# MCU-Board.net
KiCad netlist of a schematic drawn in Altium Designer
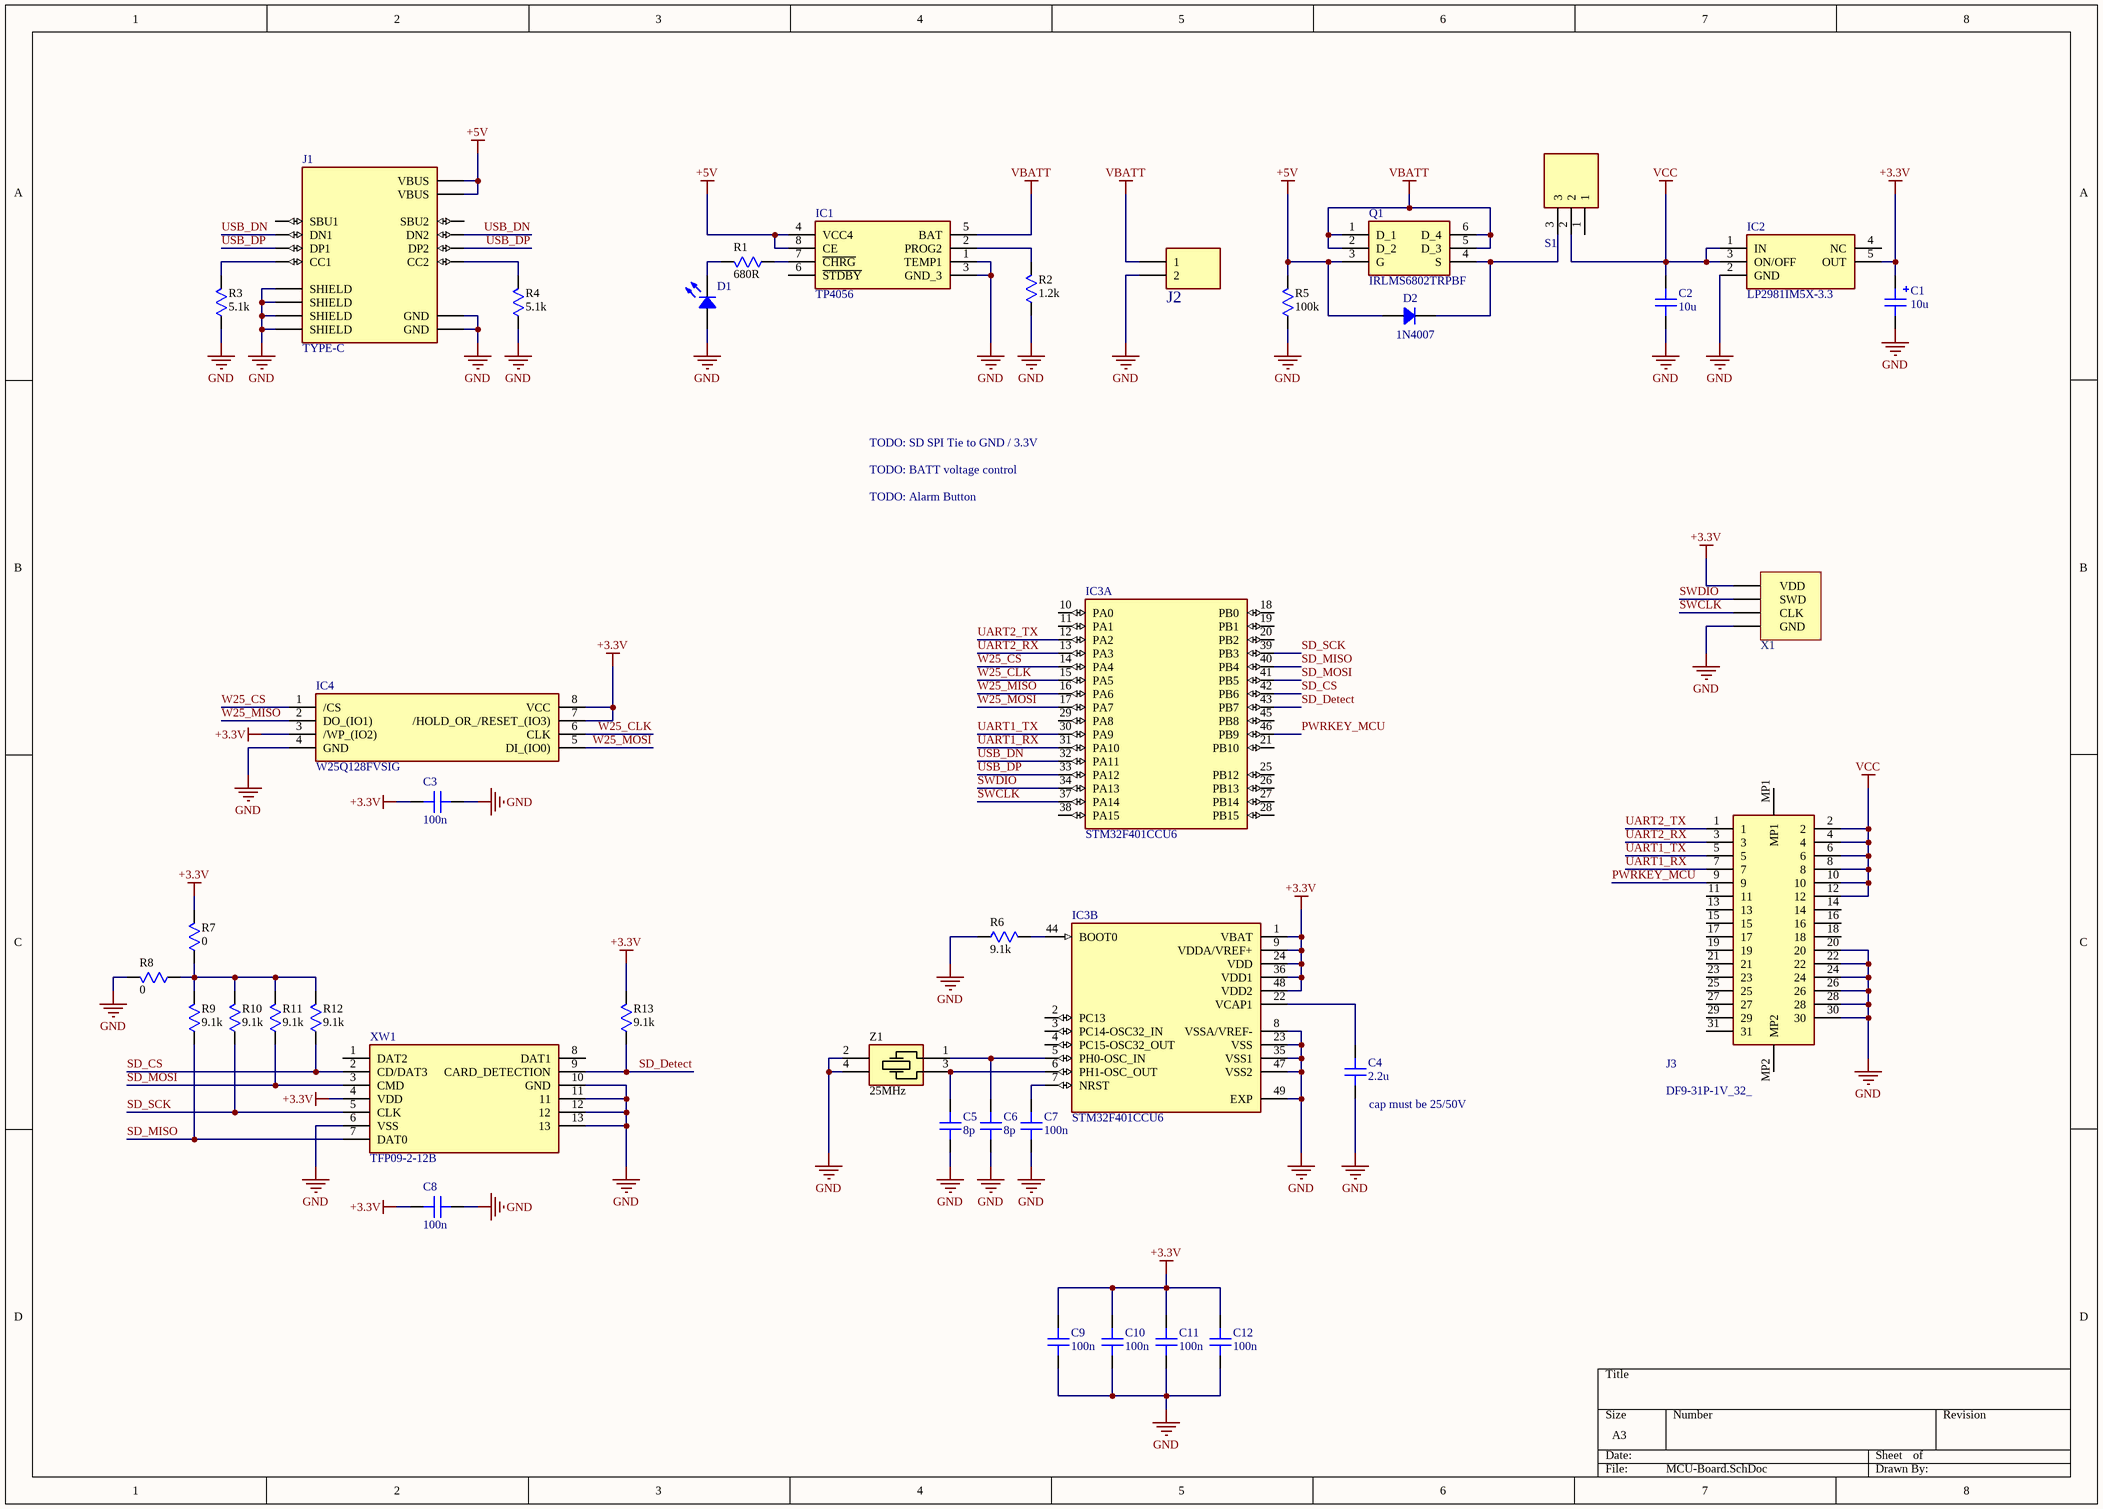
[diagram p0: MCU-Board.SchDoc]

(export (version "E")
  (design (tool "Eeschema 10.0.6"))
  (components
    (comp (ref "C1")
      (value "10u")
      (footprint "PcbLib:CAP: TANTAL-A")
      (description "SMD Capacitor Polar")
      (libsource (lib "Schlib") (part "Capacitor_polar"))
    )
    (comp (ref "C2")
      (value "10u")
      (footprint "PcbLib:CAP: 0805")
      (description "SMD Capacitor")
      (libsource (lib "Schlib") (part "Capacitor"))
    )
    (comp (ref "C3")
      (value "100n")
      (footprint "PcbLib:CAP: 0603")
      (description "SMD Capacitor")
      (libsource (lib "Schlib") (part "Capacitor"))
    )
    (comp (ref "C4")
      (value "2.2u")
      (footprint "PcbLib:CAP: 0805")
      (description "SMD Capacitor")
      (libsource (lib "Schlib") (part "Capacitor"))
    )
    (comp (ref "C5")
      (value "8p")
      (footprint "PcbLib:CAP: 0603")
      (description "SMD Capacitor")
      (libsource (lib "Schlib") (part "Capacitor"))
    )
    (comp (ref "C6")
      (value "8p")
      (footprint "PcbLib:CAP: 0603")
      (description "SMD Capacitor")
      (libsource (lib "Schlib") (part "Capacitor"))
    )
    (comp (ref "C7")
      (value "100n")
      (footprint "PcbLib:CAP: 0603")
      (description "SMD Capacitor")
      (libsource (lib "Schlib") (part "Capacitor"))
    )
    (comp (ref "C8")
      (value "100n")
      (footprint "PcbLib:CAP: 0603")
      (description "SMD Capacitor")
      (libsource (lib "Schlib") (part "Capacitor"))
    )
    (comp (ref "C9")
      (value "100n")
      (footprint "PcbLib:CAP: 0603")
      (description "SMD Capacitor")
      (libsource (lib "Schlib") (part "Capacitor"))
    )
    (comp (ref "C10")
      (value "100n")
      (footprint "PcbLib:CAP: 0603")
      (description "SMD Capacitor")
      (libsource (lib "Schlib") (part "Capacitor"))
    )
    (comp (ref "C11")
      (value "100n")
      (footprint "PcbLib:CAP: 0603")
      (description "SMD Capacitor")
      (libsource (lib "Schlib") (part "Capacitor"))
    )
    (comp (ref "C12")
      (value "100n")
      (footprint "PcbLib:CAP: 0603")
      (description "SMD Capacitor")
      (libsource (lib "Schlib") (part "Capacitor"))
    )
    (comp (ref "D1")
      (value "~")
      (footprint "PcbLib:LED 0603_1608")
      (description "Chip LED")
      (libsource (lib "Schlib") (part "LED"))
    )
    (comp (ref "D2")
      (value "1N4007")
      (footprint "PcbLib:DIODE: SMA")
      (description "Rectifier Diode")
      (libsource (lib "Schlib") (part "Diode"))
    )
    (comp (ref "IC1")
      (value "TP4056")
      (footprint "PcbLib:SOIC127P600X175-9N")
      (description "Connector")
      (libsource (lib "Schlib") (part "TP4056"))
    )
    (comp (ref "IC2")
      (value "LP2981IM5X-3.3")
      (footprint "PcbLib:SOT95P280X145-5N")
      (description "Integrated Circuit")
      (fields
        (field (name "MANUFACTURER_PART_NUMBER") "LP2981IM5X-5.0")
        (field (name "MOUSER PART NUMBER") "926-LP2981IM5X-50")
      )
      (libsource (lib "Schlib") (part "LP2981IM5X-3.3"))
    )
    (comp (ref "IC3")
      (value "STM32F401CCU6")
      (footprint "PcbLib:QFN50P700X700X60-49N-D")
      (description "Integrated Circuit")
      (fields (field (name "MOUSER PART NUMBER") "511-STM32F401CCU6"))
      (libsource (lib "Schlib") (part "STM32F401CCU6"))
    )
    (comp (ref "IC4")
      (value "W25Q128FVSIG")
      (footprint "PcbLib:SOIC127P790X216-8N")
      (description "Integrated Circuit")
      (libsource (lib "Schlib") (part "W25Q128FVSIG"))
    )
    (comp (ref "J1")
      (value "TYPE-C")
      (footprint "PcbLib:HRO_TYPE-C-31-M-12")
      (description "USB Connectors 24 Receptacle 1 8.94*7.3mm RoHS")
      (fields (field (name "MP") "TYPE-C-31-M-12"))
      (libsource (lib "Schlib") (part "TYPE-C-31-M-12"))
    )
    (comp (ref "J2")
      (value "NX1500-02SMR")
      (footprint "PcbLib:NX1500-02SMR")
      (libsource (lib "Schlib") (part "NX1500-02SMR"))
    )
    (comp (ref "J3")
      (value "DF9-31P-1V_32_")
      (footprint "PcbLib:DF931P1V32")
      (description "Connector")
      (fields
        (field (name "MANUFACTURER_PART_NUMBER") "DF9-31P-1V(32)")
        (field (name "MOUSER PART NUMBER") "798-DF9-31P-1V32")
      )
      (libsource (lib "Schlib") (part "DF9-31P-1V_32_"))
    )
    (comp (ref "Q1")
      (value "IRLMS6802TRPBF")
      (footprint "PcbLib:SOT95P280X130-6N")
      (description "MOSFET (P-Channel)")
      (fields (field (name "MOUSER PART NUMBER") "942-IRLMS6802TRPBF"))
      (libsource (lib "Schlib") (part "IRLMS6802TRPBF"))
    )
    (comp (ref "R1")
      (value "680R")
      (footprint "PcbLib:RES: 0603")
      (fields
        (field (name "MANUFACTURER") "Yageo")
        (field (name "PARTNUMBER") "RC0201JR-07100RL")
        (field (name "VALUEMANUFACTURERPARTNUMBER") "Resistor film, 680R, , 0201, 0.05W, -55...+125°C")
      )
      (libsource (lib "Schlib") (part "Resistor"))
    )
    (comp (ref "R2")
      (value "1.2k")
      (footprint "PcbLib:RES: 0805")
      (fields
        (field (name "MANUFACTURER") "Yageo")
        (field (name "PARTNUMBER") "RC0201JR-07100RL")
        (field (name "VALUEMANUFACTURERPARTNUMBER") "Resistor film, 1.2k, , 0201, 0.05W, -55...+125°C")
      )
      (libsource (lib "Schlib") (part "Resistor"))
    )
    (comp (ref "R3")
      (value "5.1k")
      (footprint "PcbLib:RES: 0603")
      (fields
        (field (name "MANUFACTURER") "Yageo")
        (field (name "PARTNUMBER") "RC0201JR-07100RL")
        (field (name "VALUEMANUFACTURERPARTNUMBER") "Resistor film, 5.1k, , 0201, 0.05W, -55...+125°C")
      )
      (libsource (lib "Schlib") (part "Resistor"))
    )
    (comp (ref "R4")
      (value "5.1k")
      (footprint "PcbLib:RES: 0603")
      (fields
        (field (name "MANUFACTURER") "Yageo")
        (field (name "PARTNUMBER") "RC0201JR-07100RL")
        (field (name "VALUEMANUFACTURERPARTNUMBER") "Resistor film, 5.1k, , 0201, 0.05W, -55...+125°C")
      )
      (libsource (lib "Schlib") (part "Resistor"))
    )
    (comp (ref "R5")
      (value "100k")
      (footprint "PcbLib:RES: 0603")
      (fields
        (field (name "MANUFACTURER") "Yageo")
        (field (name "PARTNUMBER") "RC0201JR-07100RL")
        (field (name "VALUEMANUFACTURERPARTNUMBER") "Resistor film, 100k, , 0201, 0.05W, -55...+125°C")
      )
      (libsource (lib "Schlib") (part "Resistor"))
    )
    (comp (ref "R6")
      (value "9.1k")
      (footprint "PcbLib:RES: 0603")
      (fields
        (field (name "MANUFACTURER") "Yageo")
        (field (name "PARTNUMBER") "RC0201JR-07100RL")
        (field (name "VALUEMANUFACTURERPARTNUMBER") "Resistor film, 9.1k, , 0201, 0.05W, -55...+125°C")
      )
      (libsource (lib "Schlib") (part "Resistor"))
    )
    (comp (ref "R7")
      (value "0")
      (footprint "PcbLib:RES: 0603")
      (fields
        (field (name "MANUFACTURER") "Yageo")
        (field (name "PARTNUMBER") "RC0201JR-07100RL")
        (field (name "VALUEMANUFACTURERPARTNUMBER") "Resistor film, 0, , 0201, 0.05W, -55...+125°C")
      )
      (libsource (lib "Schlib") (part "Resistor"))
    )
    (comp (ref "R8")
      (value "0")
      (footprint "PcbLib:RES: 0603")
      (fields
        (field (name "MANUFACTURER") "Yageo")
        (field (name "PARTNUMBER") "RC0201JR-07100RL")
        (field (name "VALUEMANUFACTURERPARTNUMBER") "Resistor film, 0, , 0201, 0.05W, -55...+125°C")
      )
      (libsource (lib "Schlib") (part "Resistor"))
    )
    (comp (ref "R9")
      (value "9.1k")
      (footprint "PcbLib:RES: 0603")
      (fields
        (field (name "MANUFACTURER") "Yageo")
        (field (name "PARTNUMBER") "RC0201JR-07100RL")
        (field (name "VALUEMANUFACTURERPARTNUMBER") "Resistor film, 9.1k, , 0201, 0.05W, -55...+125°C")
      )
      (libsource (lib "Schlib") (part "Resistor"))
    )
    (comp (ref "R10")
      (value "9.1k")
      (footprint "PcbLib:RES: 0603")
      (fields
        (field (name "MANUFACTURER") "Yageo")
        (field (name "PARTNUMBER") "RC0201JR-07100RL")
        (field (name "VALUEMANUFACTURERPARTNUMBER") "Resistor film, 9.1k, , 0201, 0.05W, -55...+125°C")
      )
      (libsource (lib "Schlib") (part "Resistor"))
    )
    (comp (ref "R11")
      (value "9.1k")
      (footprint "PcbLib:RES: 0603")
      (fields
        (field (name "MANUFACTURER") "Yageo")
        (field (name "PARTNUMBER") "RC0201JR-07100RL")
        (field (name "VALUEMANUFACTURERPARTNUMBER") "Resistor film, 9.1k, , 0201, 0.05W, -55...+125°C")
      )
      (libsource (lib "Schlib") (part "Resistor"))
    )
    (comp (ref "R12")
      (value "9.1k")
      (footprint "PcbLib:RES: 0603")
      (fields
        (field (name "MANUFACTURER") "Yageo")
        (field (name "PARTNUMBER") "RC0201JR-07100RL")
        (field (name "VALUEMANUFACTURERPARTNUMBER") "Resistor film, 9.1k, , 0201, 0.05W, -55...+125°C")
      )
      (libsource (lib "Schlib") (part "Resistor"))
    )
    (comp (ref "R13")
      (value "9.1k")
      (footprint "PcbLib:RES: 0603")
      (fields
        (field (name "MANUFACTURER") "Yageo")
        (field (name "PARTNUMBER") "RC0201JR-07100RL")
        (field (name "VALUEMANUFACTURERPARTNUMBER") "Resistor film, 9.1k, , 0201, 0.05W, -55...+125°C")
      )
      (libsource (lib "Schlib") (part "Resistor"))
    )
    (comp (ref "S1")
      (value "OS102011MA1QN1")
      (footprint "PcbLib:OS102011MA1QN1")
      (description "Switch")
      (fields (field (name "MOUSER PART NUMBER") "611-OS102011MA1QN1"))
      (libsource (lib "Schlib") (part "OS102011MA1QN1"))
    )
    (comp (ref "X1")
      (value "~")
      (footprint "PcbLib:CON: PLS-4R")
      (description "SWD Interface")
      (libsource (lib "Schlib") (part "Connector SWD"))
    )
    (comp (ref "XW1")
      (value "TFP09-2-12B")
      (footprint "PcbLib:TFP09212B")
      (description "Connector")
      (libsource (lib "Schlib") (part "TFP09-2-12B"))
    )
    (comp (ref "Z1")
      (value "~")
      (footprint "PcbLib:OSC: 3225")
      (fields
        (field (name "MANUFACTURER") "Murata Electronics")
        (field (name "PARTNUMBER") "XRCGB25M000F0L00R0")
        (field (name "VALUEMANUFACTURERPARTNUMBER") "Crystal, 25MHz, 6pF, ±50ppm, case 2016, -30...+85°C")
        (field (name "FREQUENCY") "25MHz")
      )
      (libsource (lib "Schlib") (part "Crystal"))
    )
  )
  (nets
    (net (code "1") (name "+3.3V") (class "Default")
      (node (ref "C1") (pin "1") (pinfunction "1_1") (pintype "passive"))
      (node (ref "C10") (pin "2") (pinfunction "2_2") (pintype "passive"))
      (node (ref "C11") (pin "2") (pinfunction "2_2") (pintype "passive"))
      (node (ref "C12") (pin "2") (pinfunction "2_2") (pintype "passive"))
      (node (ref "C3") (pin "2") (pinfunction "2_2") (pintype "passive"))
      (node (ref "C8") (pin "2") (pinfunction "2_2") (pintype "passive"))
      (node (ref "C9") (pin "2") (pinfunction "2_2") (pintype "passive"))
      (node (ref "IC2") (pin "5") (pinfunction "OUT_5") (pintype "passive"))
      (node (ref "IC3") (pin "1") (pinfunction "VBAT_1") (pintype "power_in"))
      (node (ref "IC3") (pin "24") (pinfunction "VDD_24") (pintype "power_in"))
      (node (ref "IC3") (pin "36") (pinfunction "VDD1_36") (pintype "power_in"))
      (node (ref "IC3") (pin "48") (pinfunction "VDD2_48") (pintype "power_in"))
      (node (ref "IC3") (pin "9") (pinfunction "VDDA/VREF+_9") (pintype "power_in"))
      (node (ref "IC4") (pin "3") (pinfunction "/WP_(IO2)_3") (pintype "passive"))
      (node (ref "IC4") (pin "7") (pinfunction "/HOLD_OR_/RESET_(IO3)_7") (pintype "passive"))
      (node (ref "IC4") (pin "8") (pinfunction "VCC_8") (pintype "passive"))
      (node (ref "R13") (pin "2") (pinfunction "2_2") (pintype "passive"))
      (node (ref "R7") (pin "2") (pinfunction "2_2") (pintype "passive"))
      (node (ref "X1") (pin "1") (pinfunction "VDD_1") (pintype "power_in"))
      (node (ref "XW1") (pin "4") (pinfunction "VDD_4") (pintype "passive"))
    )
    (net (code "2") (name "+5V") (class "Default")
      (node (ref "D2") (pin "1") (pinfunction "1_1") (pintype "passive"))
      (node (ref "IC1") (pin "4") (pinfunction "VCC4_4") (pintype "passive"))
      (node (ref "IC1") (pin "8") (pinfunction "CE_8") (pintype "passive"))
      (node (ref "J1") (pin "A4B9") (pinfunction "VBUS_A4B9") (pintype "power_in"))
      (node (ref "J1") (pin "B4A9") (pinfunction "VBUS_B4A9") (pintype "power_in"))
      (node (ref "Q1") (pin "3") (pinfunction "G_3") (pintype "passive"))
      (node (ref "R5") (pin "2") (pinfunction "2_2") (pintype "passive"))
    )
    (net (code "3") (name "/PWRKEY_MCU") (class "Default")
      (node (ref "IC3") (pin "46") (pinfunction "PB9_46") (pintype "bidirectional"))
      (node (ref "J3") (pin "9") (pinfunction "9_9") (pintype "passive"))
    )
    (net (code "4") (name "/SD_CS") (class "Default")
      (node (ref "IC3") (pin "42") (pinfunction "PB6_42") (pintype "bidirectional"))
      (node (ref "R12") (pin "1") (pinfunction "1_1") (pintype "passive"))
      (node (ref "XW1") (pin "2") (pinfunction "CD/DAT3_2") (pintype "passive"))
    )
    (net (code "5") (name "/SD_Detect") (class "Default")
      (node (ref "IC3") (pin "43") (pinfunction "PB7_43") (pintype "bidirectional"))
      (node (ref "R13") (pin "1") (pinfunction "1_1") (pintype "passive"))
      (node (ref "XW1") (pin "9") (pinfunction "CARD_DETECTION_9") (pintype "passive"))
    )
    (net (code "6") (name "/SD_MISO") (class "Default")
      (node (ref "IC3") (pin "40") (pinfunction "PB4_40") (pintype "bidirectional"))
      (node (ref "R9") (pin "1") (pinfunction "1_1") (pintype "passive"))
      (node (ref "XW1") (pin "7") (pinfunction "DAT0_7") (pintype "passive"))
    )
    (net (code "7") (name "/SD_MOSI") (class "Default")
      (node (ref "IC3") (pin "41") (pinfunction "PB5_41") (pintype "bidirectional"))
      (node (ref "R11") (pin "1") (pinfunction "1_1") (pintype "passive"))
      (node (ref "XW1") (pin "3") (pinfunction "CMD_3") (pintype "passive"))
    )
    (net (code "8") (name "/SD_SCK") (class "Default")
      (node (ref "IC3") (pin "39") (pinfunction "PB3_39") (pintype "bidirectional"))
      (node (ref "R10") (pin "1") (pinfunction "1_1") (pintype "passive"))
      (node (ref "XW1") (pin "5") (pinfunction "CLK_5") (pintype "passive"))
    )
    (net (code "9") (name "/SWCLK") (class "Default")
      (node (ref "IC3") (pin "37") (pinfunction "PA14_37") (pintype "bidirectional"))
      (node (ref "X1") (pin "3") (pinfunction "CLK_3") (pintype "passive"))
    )
    (net (code "10") (name "/SWDIO") (class "Default")
      (node (ref "IC3") (pin "34") (pinfunction "PA13_34") (pintype "bidirectional"))
      (node (ref "X1") (pin "2") (pinfunction "SWD_2") (pintype "passive"))
    )
    (net (code "11") (name "/UART1_RX") (class "Default")
      (node (ref "IC3") (pin "31") (pinfunction "PA10_31") (pintype "bidirectional"))
      (node (ref "J3") (pin "7") (pinfunction "7_7") (pintype "passive"))
    )
    (net (code "12") (name "/UART1_TX") (class "Default")
      (node (ref "IC3") (pin "30") (pinfunction "PA9_30") (pintype "bidirectional"))
      (node (ref "J3") (pin "5") (pinfunction "5_5") (pintype "passive"))
    )
    (net (code "13") (name "/UART2_RX") (class "Default")
      (node (ref "IC3") (pin "13") (pinfunction "PA3_13") (pintype "bidirectional"))
      (node (ref "J3") (pin "3") (pinfunction "3_3") (pintype "passive"))
    )
    (net (code "14") (name "/UART2_TX") (class "Default")
      (node (ref "IC3") (pin "12") (pinfunction "PA2_12") (pintype "bidirectional"))
      (node (ref "J3") (pin "1") (pinfunction "1_1") (pintype "passive"))
    )
    (net (code "15") (name "/USB_DN") (class "Default")
      (node (ref "IC3") (pin "32") (pinfunction "PA11_32") (pintype "bidirectional"))
      (node (ref "J1") (pin "A7") (pinfunction "DN1_A7") (pintype "bidirectional"))
      (node (ref "J1") (pin "B7") (pinfunction "DN2_B7") (pintype "bidirectional"))
    )
    (net (code "16") (name "/USB_DP") (class "Default")
      (node (ref "IC3") (pin "33") (pinfunction "PA12_33") (pintype "bidirectional"))
      (node (ref "J1") (pin "A6") (pinfunction "DP1_A6") (pintype "bidirectional"))
      (node (ref "J1") (pin "B6") (pinfunction "DP2_B6") (pintype "bidirectional"))
    )
    (net (code "17") (name "/W25_CLK") (class "Default")
      (node (ref "IC3") (pin "15") (pinfunction "PA5_15") (pintype "bidirectional"))
      (node (ref "IC4") (pin "6") (pinfunction "CLK_6") (pintype "passive"))
    )
    (net (code "18") (name "/W25_CS") (class "Default")
      (node (ref "IC3") (pin "14") (pinfunction "PA4_14") (pintype "bidirectional"))
      (node (ref "IC4") (pin "1") (pinfunction "/CS_1") (pintype "passive"))
    )
    (net (code "19") (name "/W25_MISO") (class "Default")
      (node (ref "IC3") (pin "16") (pinfunction "PA6_16") (pintype "bidirectional"))
      (node (ref "IC4") (pin "2") (pinfunction "DO_(IO1)_2") (pintype "passive"))
    )
    (net (code "20") (name "/W25_MOSI") (class "Default")
      (node (ref "IC3") (pin "17") (pinfunction "PA7_17") (pintype "bidirectional"))
      (node (ref "IC4") (pin "5") (pinfunction "DI_(IO0)_5") (pintype "passive"))
    )
    (net (code "21") (name "GND") (class "Default")
      (node (ref "C1") (pin "2") (pinfunction "2_2") (pintype "passive"))
      (node (ref "C10") (pin "1") (pinfunction "1_1") (pintype "passive"))
      (node (ref "C11") (pin "1") (pinfunction "1_1") (pintype "passive"))
      (node (ref "C12") (pin "1") (pinfunction "1_1") (pintype "passive"))
      (node (ref "C2") (pin "1") (pinfunction "1_1") (pintype "passive"))
      (node (ref "C3") (pin "1") (pinfunction "1_1") (pintype "passive"))
      (node (ref "C4") (pin "1") (pinfunction "1_1") (pintype "passive"))
      (node (ref "C5") (pin "1") (pinfunction "1_1") (pintype "passive"))
      (node (ref "C6") (pin "2") (pinfunction "2_2") (pintype "passive"))
      (node (ref "C7") (pin "1") (pinfunction "1_1") (pintype "passive"))
      (node (ref "C8") (pin "1") (pinfunction "1_1") (pintype "passive"))
      (node (ref "C9") (pin "1") (pinfunction "1_1") (pintype "passive"))
      (node (ref "D1") (pin "1") (pinfunction "1_1") (pintype "passive"))
      (node (ref "IC1") (pin "1") (pinfunction "TEMP1_1") (pintype "passive"))
      (node (ref "IC1") (pin "3") (pinfunction "GND_3_3") (pintype "passive"))
      (node (ref "IC2") (pin "2") (pinfunction "GND_2") (pintype "passive"))
      (node (ref "IC3") (pin "23") (pinfunction "VSS_23") (pintype "power_in"))
      (node (ref "IC3") (pin "35") (pinfunction "VSS1_35") (pintype "power_in"))
      (node (ref "IC3") (pin "47") (pinfunction "VSS2_47") (pintype "power_in"))
      (node (ref "IC3") (pin "49") (pinfunction "EXP_49") (pintype "power_in"))
      (node (ref "IC3") (pin "8") (pinfunction "VSSA/VREF-_8") (pintype "power_in"))
      (node (ref "IC4") (pin "4") (pinfunction "GND_4") (pintype "passive"))
      (node (ref "J1") (pin "A1B12") (pinfunction "GND_A1B12") (pintype "power_in"))
      (node (ref "J1") (pin "B1A12") (pinfunction "GND_B1A12") (pintype "power_in"))
      (node (ref "J1") (pin "S1") (pinfunction "SHIELD_S1") (pintype "passive"))
      (node (ref "J1") (pin "S2") (pinfunction "SHIELD_S2") (pintype "passive"))
      (node (ref "J1") (pin "S3") (pinfunction "SHIELD_S3") (pintype "passive"))
      (node (ref "J1") (pin "S4") (pinfunction "SHIELD_S4") (pintype "passive"))
      (node (ref "J2") (pin "2") (pinfunction "2_2") (pintype "passive"))
      (node (ref "J3") (pin "20") (pinfunction "20_20") (pintype "passive"))
      (node (ref "J3") (pin "22") (pinfunction "22_22") (pintype "passive"))
      (node (ref "J3") (pin "24") (pinfunction "24_24") (pintype "passive"))
      (node (ref "J3") (pin "26") (pinfunction "26_26") (pintype "passive"))
      (node (ref "J3") (pin "28") (pinfunction "28_28") (pintype "passive"))
      (node (ref "J3") (pin "30") (pinfunction "30_30") (pintype "passive"))
      (node (ref "R2") (pin "1") (pinfunction "1_1") (pintype "passive"))
      (node (ref "R3") (pin "1") (pinfunction "1_1") (pintype "passive"))
      (node (ref "R4") (pin "1") (pinfunction "1_1") (pintype "passive"))
      (node (ref "R5") (pin "1") (pinfunction "1_1") (pintype "passive"))
      (node (ref "R6") (pin "1") (pinfunction "1_1") (pintype "passive"))
      (node (ref "R8") (pin "2") (pinfunction "2_2") (pintype "passive"))
      (node (ref "X1") (pin "4") (pinfunction "GND_4") (pintype "power_in"))
      (node (ref "XW1") (pin "10") (pinfunction "GND_10") (pintype "passive"))
      (node (ref "XW1") (pin "11") (pinfunction "11_11") (pintype "passive"))
      (node (ref "XW1") (pin "12") (pinfunction "12_12") (pintype "passive"))
      (node (ref "XW1") (pin "13") (pinfunction "13_13") (pintype "passive"))
      (node (ref "XW1") (pin "6") (pinfunction "VSS_6") (pintype "passive"))
      (node (ref "Z1") (pin "2") (pinfunction "2_2") (pintype "passive"))
      (node (ref "Z1") (pin "4") (pinfunction "4_4") (pintype "passive"))
    )
    (net (code "22") (name "Net-(D1-Pad2)") (class "Default")
      (node (ref "D1") (pin "2") (pinfunction "2_2") (pintype "passive"))
      (node (ref "R1") (pin "2") (pinfunction "2_2") (pintype "passive"))
    )
    (net (code "23") (name "Net-(IC1-PROG2)") (class "Default")
      (node (ref "IC1") (pin "2") (pinfunction "PROG2_2") (pintype "passive"))
      (node (ref "R2") (pin "2") (pinfunction "2_2") (pintype "passive"))
    )
    (net (code "24") (name "Net-(IC1-~{CHRG})") (class "Default")
      (node (ref "IC1") (pin "7") (pinfunction "~{CHRG}_7") (pintype "passive"))
      (node (ref "R1") (pin "1") (pinfunction "1_1") (pintype "passive"))
    )
    (net (code "25") (name "Net-(IC3B-BOOT0)") (class "Default")
      (node (ref "IC3") (pin "44") (pinfunction "BOOT0_44") (pintype "input"))
      (node (ref "R6") (pin "2") (pinfunction "2_2") (pintype "passive"))
    )
    (net (code "26") (name "Net-(IC3B-NRST)") (class "Default")
      (node (ref "C7") (pin "2") (pinfunction "2_2") (pintype "passive"))
      (node (ref "IC3") (pin "7") (pinfunction "NRST_7") (pintype "bidirectional"))
    )
    (net (code "27") (name "Net-(IC3B-PH0-OSC_IN)") (class "Default")
      (node (ref "C6") (pin "1") (pinfunction "1_1") (pintype "passive"))
      (node (ref "IC3") (pin "5") (pinfunction "PH0-OSC_IN_5") (pintype "bidirectional"))
      (node (ref "Z1") (pin "1") (pinfunction "1_1") (pintype "passive"))
    )
    (net (code "28") (name "Net-(IC3B-PH1-OSC_OUT)") (class "Default")
      (node (ref "C5") (pin "2") (pinfunction "2_2") (pintype "passive"))
      (node (ref "IC3") (pin "6") (pinfunction "PH1-OSC_OUT_6") (pintype "bidirectional"))
      (node (ref "Z1") (pin "3") (pinfunction "3_3") (pintype "passive"))
    )
    (net (code "29") (name "Net-(IC3B-VCAP1)") (class "Default")
      (node (ref "C4") (pin "2") (pinfunction "2_2") (pintype "passive"))
      (node (ref "IC3") (pin "22") (pinfunction "VCAP1_22") (pintype "power_in"))
    )
    (net (code "30") (name "Net-(J1-CC1)") (class "Default")
      (node (ref "J1") (pin "A5") (pinfunction "CC1_A5") (pintype "bidirectional"))
      (node (ref "R3") (pin "2") (pinfunction "2_2") (pintype "passive"))
    )
    (net (code "31") (name "Net-(J1-CC2)") (class "Default")
      (node (ref "J1") (pin "B5") (pinfunction "CC2_B5") (pintype "bidirectional"))
      (node (ref "R4") (pin "2") (pinfunction "2_2") (pintype "passive"))
    )
    (net (code "32") (name "Net-(Q1-S)") (class "Default")
      (node (ref "D2") (pin "2") (pinfunction "2_2") (pintype "passive"))
      (node (ref "Q1") (pin "4") (pinfunction "S_4") (pintype "passive"))
      (node (ref "S1") (pin "3") (pinfunction "3_3") (pintype "passive"))
    )
    (net (code "33") (name "Net-(R10-Pad2)") (class "Default")
      (node (ref "R10") (pin "2") (pinfunction "2_2") (pintype "passive"))
      (node (ref "R11") (pin "2") (pinfunction "2_2") (pintype "passive"))
      (node (ref "R12") (pin "2") (pinfunction "2_2") (pintype "passive"))
      (node (ref "R7") (pin "1") (pinfunction "1_1") (pintype "passive"))
      (node (ref "R8") (pin "1") (pinfunction "1_1") (pintype "passive"))
      (node (ref "R9") (pin "2") (pinfunction "2_2") (pintype "passive"))
    )
    (net (code "34") (name "VBATT") (class "Default")
      (node (ref "IC1") (pin "5") (pinfunction "BAT_5") (pintype "passive"))
      (node (ref "J2") (pin "1") (pinfunction "1_1") (pintype "passive"))
      (node (ref "Q1") (pin "1") (pinfunction "D_1_1") (pintype "passive"))
      (node (ref "Q1") (pin "2") (pinfunction "D_2_2") (pintype "passive"))
      (node (ref "Q1") (pin "5") (pinfunction "D_3_5") (pintype "passive"))
      (node (ref "Q1") (pin "6") (pinfunction "D_4_6") (pintype "passive"))
    )
    (net (code "35") (name "VCC") (class "Default")
      (node (ref "C2") (pin "2") (pinfunction "2_2") (pintype "passive"))
      (node (ref "IC2") (pin "1") (pinfunction "IN_1") (pintype "passive"))
      (node (ref "IC2") (pin "3") (pinfunction "ON/OFF_3") (pintype "passive"))
      (node (ref "J3") (pin "10") (pinfunction "10_10") (pintype "passive"))
      (node (ref "J3") (pin "12") (pinfunction "12_12") (pintype "passive"))
      (node (ref "J3") (pin "2") (pinfunction "2_2") (pintype "passive"))
      (node (ref "J3") (pin "4") (pinfunction "4_4") (pintype "passive"))
      (node (ref "J3") (pin "6") (pinfunction "6_6") (pintype "passive"))
      (node (ref "J3") (pin "8") (pinfunction "8_8") (pintype "passive"))
      (node (ref "S1") (pin "2") (pinfunction "2_2") (pintype "passive"))
    )
    (net (code "36") (name "unconnected-(IC1-~{STDBY}-Pad6)") (class "Default")
      (node (ref "IC1") (pin "6") (pinfunction "~{STDBY}_6") (pintype "passive"))
    )
    (net (code "37") (name "unconnected-(IC2-NC-Pad4)") (class "Default")
      (node (ref "IC2") (pin "4") (pinfunction "NC_4") (pintype "passive"))
    )
    (net (code "38") (name "unconnected-(IC3A-PA0-Pad10)") (class "Default")
      (node (ref "IC3") (pin "10") (pinfunction "PA0_10") (pintype "bidirectional"))
    )
    (net (code "39") (name "unconnected-(IC3A-PA1-Pad11)") (class "Default")
      (node (ref "IC3") (pin "11") (pinfunction "PA1_11") (pintype "bidirectional"))
    )
    (net (code "40") (name "unconnected-(IC3A-PA8-Pad29)") (class "Default")
      (node (ref "IC3") (pin "29") (pinfunction "PA8_29") (pintype "bidirectional"))
    )
    (net (code "41") (name "unconnected-(IC3A-PA15-Pad38)") (class "Default")
      (node (ref "IC3") (pin "38") (pinfunction "PA15_38") (pintype "bidirectional"))
    )
    (net (code "42") (name "unconnected-(IC3A-PB0-Pad18)") (class "Default")
      (node (ref "IC3") (pin "18") (pinfunction "PB0_18") (pintype "bidirectional"))
    )
    (net (code "43") (name "unconnected-(IC3A-PB1-Pad19)") (class "Default")
      (node (ref "IC3") (pin "19") (pinfunction "PB1_19") (pintype "bidirectional"))
    )
    (net (code "44") (name "unconnected-(IC3A-PB2-Pad20)") (class "Default")
      (node (ref "IC3") (pin "20") (pinfunction "PB2_20") (pintype "bidirectional"))
    )
    (net (code "45") (name "unconnected-(IC3A-PB8-Pad45)") (class "Default")
      (node (ref "IC3") (pin "45") (pinfunction "PB8_45") (pintype "bidirectional"))
    )
    (net (code "46") (name "unconnected-(IC3A-PB10-Pad21)") (class "Default")
      (node (ref "IC3") (pin "21") (pinfunction "PB10_21") (pintype "bidirectional"))
    )
    (net (code "47") (name "unconnected-(IC3A-PB12-Pad25)") (class "Default")
      (node (ref "IC3") (pin "25") (pinfunction "PB12_25") (pintype "bidirectional"))
    )
    (net (code "48") (name "unconnected-(IC3A-PB13-Pad26)") (class "Default")
      (node (ref "IC3") (pin "26") (pinfunction "PB13_26") (pintype "bidirectional"))
    )
    (net (code "49") (name "unconnected-(IC3A-PB14-Pad27)") (class "Default")
      (node (ref "IC3") (pin "27") (pinfunction "PB14_27") (pintype "bidirectional"))
    )
    (net (code "50") (name "unconnected-(IC3A-PB15-Pad28)") (class "Default")
      (node (ref "IC3") (pin "28") (pinfunction "PB15_28") (pintype "bidirectional"))
    )
    (net (code "51") (name "unconnected-(IC3B-PC13-Pad2)") (class "Default")
      (node (ref "IC3") (pin "2") (pinfunction "PC13_2") (pintype "bidirectional"))
    )
    (net (code "52") (name "unconnected-(IC3B-PC14-OSC32_IN-Pad3)") (class "Default")
      (node (ref "IC3") (pin "3") (pinfunction "PC14-OSC32_IN_3") (pintype "bidirectional"))
    )
    (net (code "53") (name "unconnected-(IC3B-PC15-OSC32_OUT-Pad4)") (class "Default")
      (node (ref "IC3") (pin "4") (pinfunction "PC15-OSC32_OUT_4") (pintype "bidirectional"))
    )
    (net (code "54") (name "unconnected-(J1-SBU1-PadA8)") (class "Default")
      (node (ref "J1") (pin "A8") (pinfunction "SBU1_A8") (pintype "bidirectional"))
    )
    (net (code "55") (name "unconnected-(J1-SBU2-PadB8)") (class "Default")
      (node (ref "J1") (pin "B8") (pinfunction "SBU2_B8") (pintype "bidirectional"))
    )
    (net (code "56") (name "unconnected-(J3-Pad11)") (class "Default")
      (node (ref "J3") (pin "11") (pinfunction "11_11") (pintype "passive"))
    )
    (net (code "57") (name "unconnected-(J3-Pad13)") (class "Default")
      (node (ref "J3") (pin "13") (pinfunction "13_13") (pintype "passive"))
    )
    (net (code "58") (name "unconnected-(J3-Pad14)") (class "Default")
      (node (ref "J3") (pin "14") (pinfunction "14_14") (pintype "passive"))
    )
    (net (code "59") (name "unconnected-(J3-Pad15)") (class "Default")
      (node (ref "J3") (pin "15") (pinfunction "15_15") (pintype "passive"))
    )
    (net (code "60") (name "unconnected-(J3-Pad16)") (class "Default")
      (node (ref "J3") (pin "16") (pinfunction "16_16") (pintype "passive"))
    )
    (net (code "61") (name "unconnected-(J3-Pad17)") (class "Default")
      (node (ref "J3") (pin "17") (pinfunction "17_17") (pintype "passive"))
    )
    (net (code "62") (name "unconnected-(J3-Pad18)") (class "Default")
      (node (ref "J3") (pin "18") (pinfunction "18_18") (pintype "passive"))
    )
    (net (code "63") (name "unconnected-(J3-Pad19)") (class "Default")
      (node (ref "J3") (pin "19") (pinfunction "19_19") (pintype "passive"))
    )
    (net (code "64") (name "unconnected-(J3-Pad21)") (class "Default")
      (node (ref "J3") (pin "21") (pinfunction "21_21") (pintype "passive"))
    )
    (net (code "65") (name "unconnected-(J3-Pad23)") (class "Default")
      (node (ref "J3") (pin "23") (pinfunction "23_23") (pintype "passive"))
    )
    (net (code "66") (name "unconnected-(J3-Pad25)") (class "Default")
      (node (ref "J3") (pin "25") (pinfunction "25_25") (pintype "passive"))
    )
    (net (code "67") (name "unconnected-(J3-Pad27)") (class "Default")
      (node (ref "J3") (pin "27") (pinfunction "27_27") (pintype "passive"))
    )
    (net (code "68") (name "unconnected-(J3-Pad29)") (class "Default")
      (node (ref "J3") (pin "29") (pinfunction "29_29") (pintype "passive"))
    )
    (net (code "69") (name "unconnected-(J3-Pad31)") (class "Default")
      (node (ref "J3") (pin "31") (pinfunction "31_31") (pintype "passive"))
    )
    (net (code "70") (name "unconnected-(J3-PadMP1)") (class "Default")
      (node (ref "J3") (pin "MP1") (pinfunction "MP1_MP1") (pintype "passive"))
    )
    (net (code "71") (name "unconnected-(J3-PadMP2)") (class "Default")
      (node (ref "J3") (pin "MP2") (pinfunction "MP2_MP2") (pintype "passive"))
    )
    (net (code "72") (name "unconnected-(S1-Pad1)") (class "Default")
      (node (ref "S1") (pin "1") (pinfunction "1_1") (pintype "passive"))
    )
    (net (code "73") (name "unconnected-(XW1-DAT1-Pad8)") (class "Default")
      (node (ref "XW1") (pin "8") (pinfunction "DAT1_8") (pintype "passive"))
    )
    (net (code "74") (name "unconnected-(XW1-DAT2-Pad1)") (class "Default")
      (node (ref "XW1") (pin "1") (pinfunction "DAT2_1") (pintype "passive"))
    )
  )
)
